# 48V_0_5A_Converter.net
KiCad netlist of a schematic drawn in Altium Designer
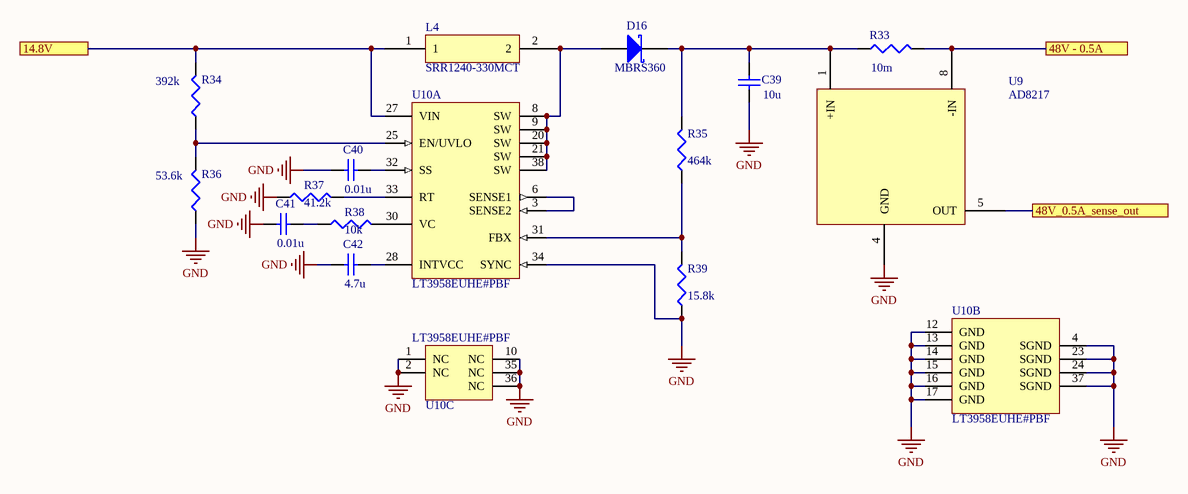
[diagram p0: 48V_0.5A_Converter.SchDoc]

(export (version "E")
  (design (tool "Eeschema 10.0.6"))
  (components
    (comp (ref "C39")
      (value "10u")
      (footprint "C1206")
      (description "Capacitor (Semiconductor SIM Model)")
      (fields (field (name "Comment") "Cap Semi") (field (name "PUBLISHER") "Altium Limited"))
      (libsource (lib "Miscellaneous Devices") (part "Cap Semi"))
    )
    (comp (ref "C40")
      (value "0.01u")
      (footprint "C1206")
      (description "Capacitor (Semiconductor SIM Model)")
      (fields (field (name "Comment") "Cap Semi") (field (name "PUBLISHER") "Altium Limited"))
      (libsource (lib "Miscellaneous Devices") (part "Cap Semi"))
    )
    (comp (ref "C41")
      (value "0.01u")
      (footprint "C1206")
      (description "Capacitor (Semiconductor SIM Model)")
      (fields (field (name "Comment") "Cap Semi") (field (name "PUBLISHER") "Altium Limited"))
      (libsource (lib "Miscellaneous Devices") (part "Cap Semi"))
    )
    (comp (ref "C42")
      (value "4.7u")
      (footprint "C1206")
      (description "Capacitor (Semiconductor SIM Model)")
      (fields (field (name "Comment") "Cap Semi") (field (name "PUBLISHER") "Altium Limited"))
      (libsource (lib "Miscellaneous Devices") (part "Cap Semi"))
    )
    (comp (ref "D16")
      (value "MBRS360")
      (footprint "SMB")
      (description "Schottky Diode")
      (fields (field (name "PUBLISHER") "Altium Limited"))
      (libsource (lib "Miscellaneous Devices") (part "D Schottky"))
    )
    (comp (ref "L4")
      (value "SRR1240-330MCT")
      (footprint "SRR1240-4R7M")
      (description "Inductor")
      (libsource (lib "Power_Board_Parts_Library_Final") (part "SRR1240-4R7MCT"))
    )
    (comp (ref "R33")
      (value "10m")
      (footprint "J1-0603")
      (description "Resistor")
      (fields (field (name "Comment") "Res3") (field (name "PUBLISHER") "Altium Limited"))
      (libsource (lib "Miscellaneous Devices") (part "Res3"))
    )
    (comp (ref "R34")
      (value "392k")
      (footprint "J1-0603")
      (description "Resistor")
      (fields (field (name "Comment") "Res3") (field (name "PUBLISHER") "Altium Limited"))
      (libsource (lib "Miscellaneous Devices") (part "Res3"))
    )
    (comp (ref "R35")
      (value "464k")
      (footprint "J1-0603")
      (description "Resistor")
      (fields (field (name "Comment") "Res3") (field (name "PUBLISHER") "Altium Limited"))
      (libsource (lib "Miscellaneous Devices") (part "Res3"))
    )
    (comp (ref "R36")
      (value "53.6k")
      (footprint "J1-0603")
      (description "Resistor")
      (fields (field (name "Comment") "Res3") (field (name "PUBLISHER") "Altium Limited"))
      (libsource (lib "Miscellaneous Devices") (part "Res3"))
    )
    (comp (ref "R37")
      (value "41.2k")
      (footprint "J1-0603")
      (description "Resistor")
      (fields (field (name "Comment") "Res3") (field (name "PUBLISHER") "Altium Limited"))
      (libsource (lib "Miscellaneous Devices") (part "Res3"))
    )
    (comp (ref "R38")
      (value "10k")
      (footprint "J1-0603")
      (description "Resistor")
      (fields (field (name "Comment") "Res3") (field (name "PUBLISHER") "Altium Limited"))
      (libsource (lib "Miscellaneous Devices") (part "Res3"))
    )
    (comp (ref "R39")
      (value "15.8k")
      (footprint "J1-0603")
      (description "Resistor")
      (fields (field (name "Comment") "Res3") (field (name "PUBLISHER") "Altium Limited"))
      (libsource (lib "Miscellaneous Devices") (part "Res3"))
    )
    (comp (ref "U9")
      (value "AD8217")
      (footprint "AD8217")
      (description "Current Shunt Moniter")
      (libsource (lib "Integrated_Library") (part "AD8217"))
    )
    (comp (ref "U10")
      (value "LT3958EUHE#PBF")
      (footprint "LT3958")
      (description "LT3958")
      (fields (field (name "MANUFACTURER") "Linear Technology"))
      (libsource (lib "Integrated_Library") (part "LT3958EUHE#PBF"))
    )
  )
  (nets
    (net (code "1") (name "/14.8V") (class "Default")
      (node (ref "L4") (pin "1") (pinfunction "1_1") (pintype "passive"))
      (node (ref "R34") (pin "2") (pinfunction "2_2") (pintype "passive"))
      (node (ref "U10") (pin "27") (pinfunction "VIN_27") (pintype "power_in"))
    )
    (net (code "2") (name "/48V - 0.5A") (class "Default")
      (node (ref "R33") (pin "2") (pinfunction "2_2") (pintype "passive"))
      (node (ref "U9") (pin "8") (pinfunction "-IN_8") (pintype "passive"))
    )
    (net (code "3") (name "/48V_0.5A_sense_out") (class "Default")
      (node (ref "U9") (pin "5") (pinfunction "OUT_5") (pintype "passive"))
    )
    (net (code "4") (name "GND") (class "Default")
      (node (ref "C39") (pin "1") (pinfunction "1_1") (pintype "passive"))
      (node (ref "C40") (pin "1") (pinfunction "1_1") (pintype "passive"))
      (node (ref "C41") (pin "1") (pinfunction "1_1") (pintype "passive"))
      (node (ref "C42") (pin "1") (pinfunction "1_1") (pintype "passive"))
      (node (ref "R36") (pin "1") (pinfunction "1_1") (pintype "passive"))
      (node (ref "R37") (pin "1") (pinfunction "1_1") (pintype "passive"))
      (node (ref "R39") (pin "1") (pinfunction "1_1") (pintype "passive"))
      (node (ref "U10") (pin "1") (pinfunction "NC_1") (pintype "passive"))
      (node (ref "U10") (pin "10") (pinfunction "NC_10") (pintype "passive"))
      (node (ref "U10") (pin "12") (pinfunction "GND_12") (pintype "power_in"))
      (node (ref "U10") (pin "13") (pinfunction "GND_13") (pintype "power_in"))
      (node (ref "U10") (pin "14") (pinfunction "GND_14") (pintype "power_in"))
      (node (ref "U10") (pin "15") (pinfunction "GND_15") (pintype "power_in"))
      (node (ref "U10") (pin "16") (pinfunction "GND_16") (pintype "power_in"))
      (node (ref "U10") (pin "17") (pinfunction "GND_17") (pintype "power_in"))
      (node (ref "U10") (pin "2") (pinfunction "NC_2") (pintype "passive"))
      (node (ref "U10") (pin "23") (pinfunction "SGND_23") (pintype "power_in"))
      (node (ref "U10") (pin "24") (pinfunction "SGND_24") (pintype "power_in"))
      (node (ref "U10") (pin "34") (pinfunction "SYNC_34") (pintype "input"))
      (node (ref "U10") (pin "35") (pinfunction "NC_35") (pintype "passive"))
      (node (ref "U10") (pin "36") (pinfunction "NC_36") (pintype "passive"))
      (node (ref "U10") (pin "37") (pinfunction "SGND_37") (pintype "power_in"))
      (node (ref "U10") (pin "4") (pinfunction "SGND_4") (pintype "power_in"))
      (node (ref "U9") (pin "4") (pinfunction "GND_4") (pintype "passive"))
    )
    (net (code "5") (name "Net-(C41-Pad2)") (class "Default")
      (node (ref "C41") (pin "2") (pinfunction "2_2") (pintype "passive"))
      (node (ref "R38") (pin "1") (pinfunction "1_1") (pintype "passive"))
    )
    (net (code "6") (name "Net-(D16-A)") (class "Default")
      (node (ref "D16") (pin "1") (pinfunction "A_1") (pintype "passive"))
      (node (ref "L4") (pin "2") (pinfunction "2_2") (pintype "passive"))
      (node (ref "U10") (pin "20") (pinfunction "SW_20") (pintype "power_in"))
      (node (ref "U10") (pin "21") (pinfunction "SW_21") (pintype "power_in"))
      (node (ref "U10") (pin "38") (pinfunction "SW_38") (pintype "power_in"))
      (node (ref "U10") (pin "8") (pinfunction "SW_8") (pintype "power_in"))
      (node (ref "U10") (pin "9") (pinfunction "SW_9") (pintype "power_in"))
    )
    (net (code "7") (name "Net-(D16-K)") (class "Default")
      (node (ref "C39") (pin "2") (pinfunction "2_2") (pintype "passive"))
      (node (ref "D16") (pin "2") (pinfunction "K_2") (pintype "passive"))
      (node (ref "R33") (pin "1") (pinfunction "1_1") (pintype "passive"))
      (node (ref "R35") (pin "2") (pinfunction "2_2") (pintype "passive"))
      (node (ref "U9") (pin "1") (pinfunction "+IN_1") (pintype "passive"))
    )
    (net (code "8") (name "Net-(U10A-EN{slash}UVLO)") (class "Default")
      (node (ref "R34") (pin "1") (pinfunction "1_1") (pintype "passive"))
      (node (ref "R36") (pin "2") (pinfunction "2_2") (pintype "passive"))
      (node (ref "U10") (pin "25") (pinfunction "EN/UVLO_25") (pintype "input"))
    )
    (net (code "9") (name "Net-(U10A-FBX)") (class "Default")
      (node (ref "R35") (pin "1") (pinfunction "1_1") (pintype "passive"))
      (node (ref "R39") (pin "2") (pinfunction "2_2") (pintype "passive"))
      (node (ref "U10") (pin "31") (pinfunction "FBX_31") (pintype "input"))
    )
    (net (code "10") (name "Net-(U10A-INTVCC)") (class "Default")
      (node (ref "C42") (pin "2") (pinfunction "2_2") (pintype "passive"))
      (node (ref "U10") (pin "28") (pinfunction "INTVCC_28") (pintype "power_in"))
    )
    (net (code "11") (name "Net-(U10A-RT)") (class "Default")
      (node (ref "R37") (pin "2") (pinfunction "2_2") (pintype "passive"))
      (node (ref "U10") (pin "33") (pinfunction "RT_33") (pintype "passive"))
    )
    (net (code "12") (name "Net-(U10A-SENSE1)") (class "Default")
      (node (ref "U10") (pin "3") (pinfunction "SENSE2_3") (pintype "input"))
      (node (ref "U10") (pin "6") (pinfunction "SENSE1_6") (pintype "output"))
    )
    (net (code "13") (name "Net-(U10A-SS)") (class "Default")
      (node (ref "C40") (pin "2") (pinfunction "2_2") (pintype "passive"))
      (node (ref "U10") (pin "32") (pinfunction "SS_32") (pintype "input"))
    )
    (net (code "14") (name "Net-(U10A-VC)") (class "Default")
      (node (ref "R38") (pin "2") (pinfunction "2_2") (pintype "passive"))
      (node (ref "U10") (pin "30") (pinfunction "VC_30") (pintype "passive"))
    )
  )
)
